# EEC_Capstone-Bottom_Board.net
KiCad netlist of a schematic drawn in EasyEDA
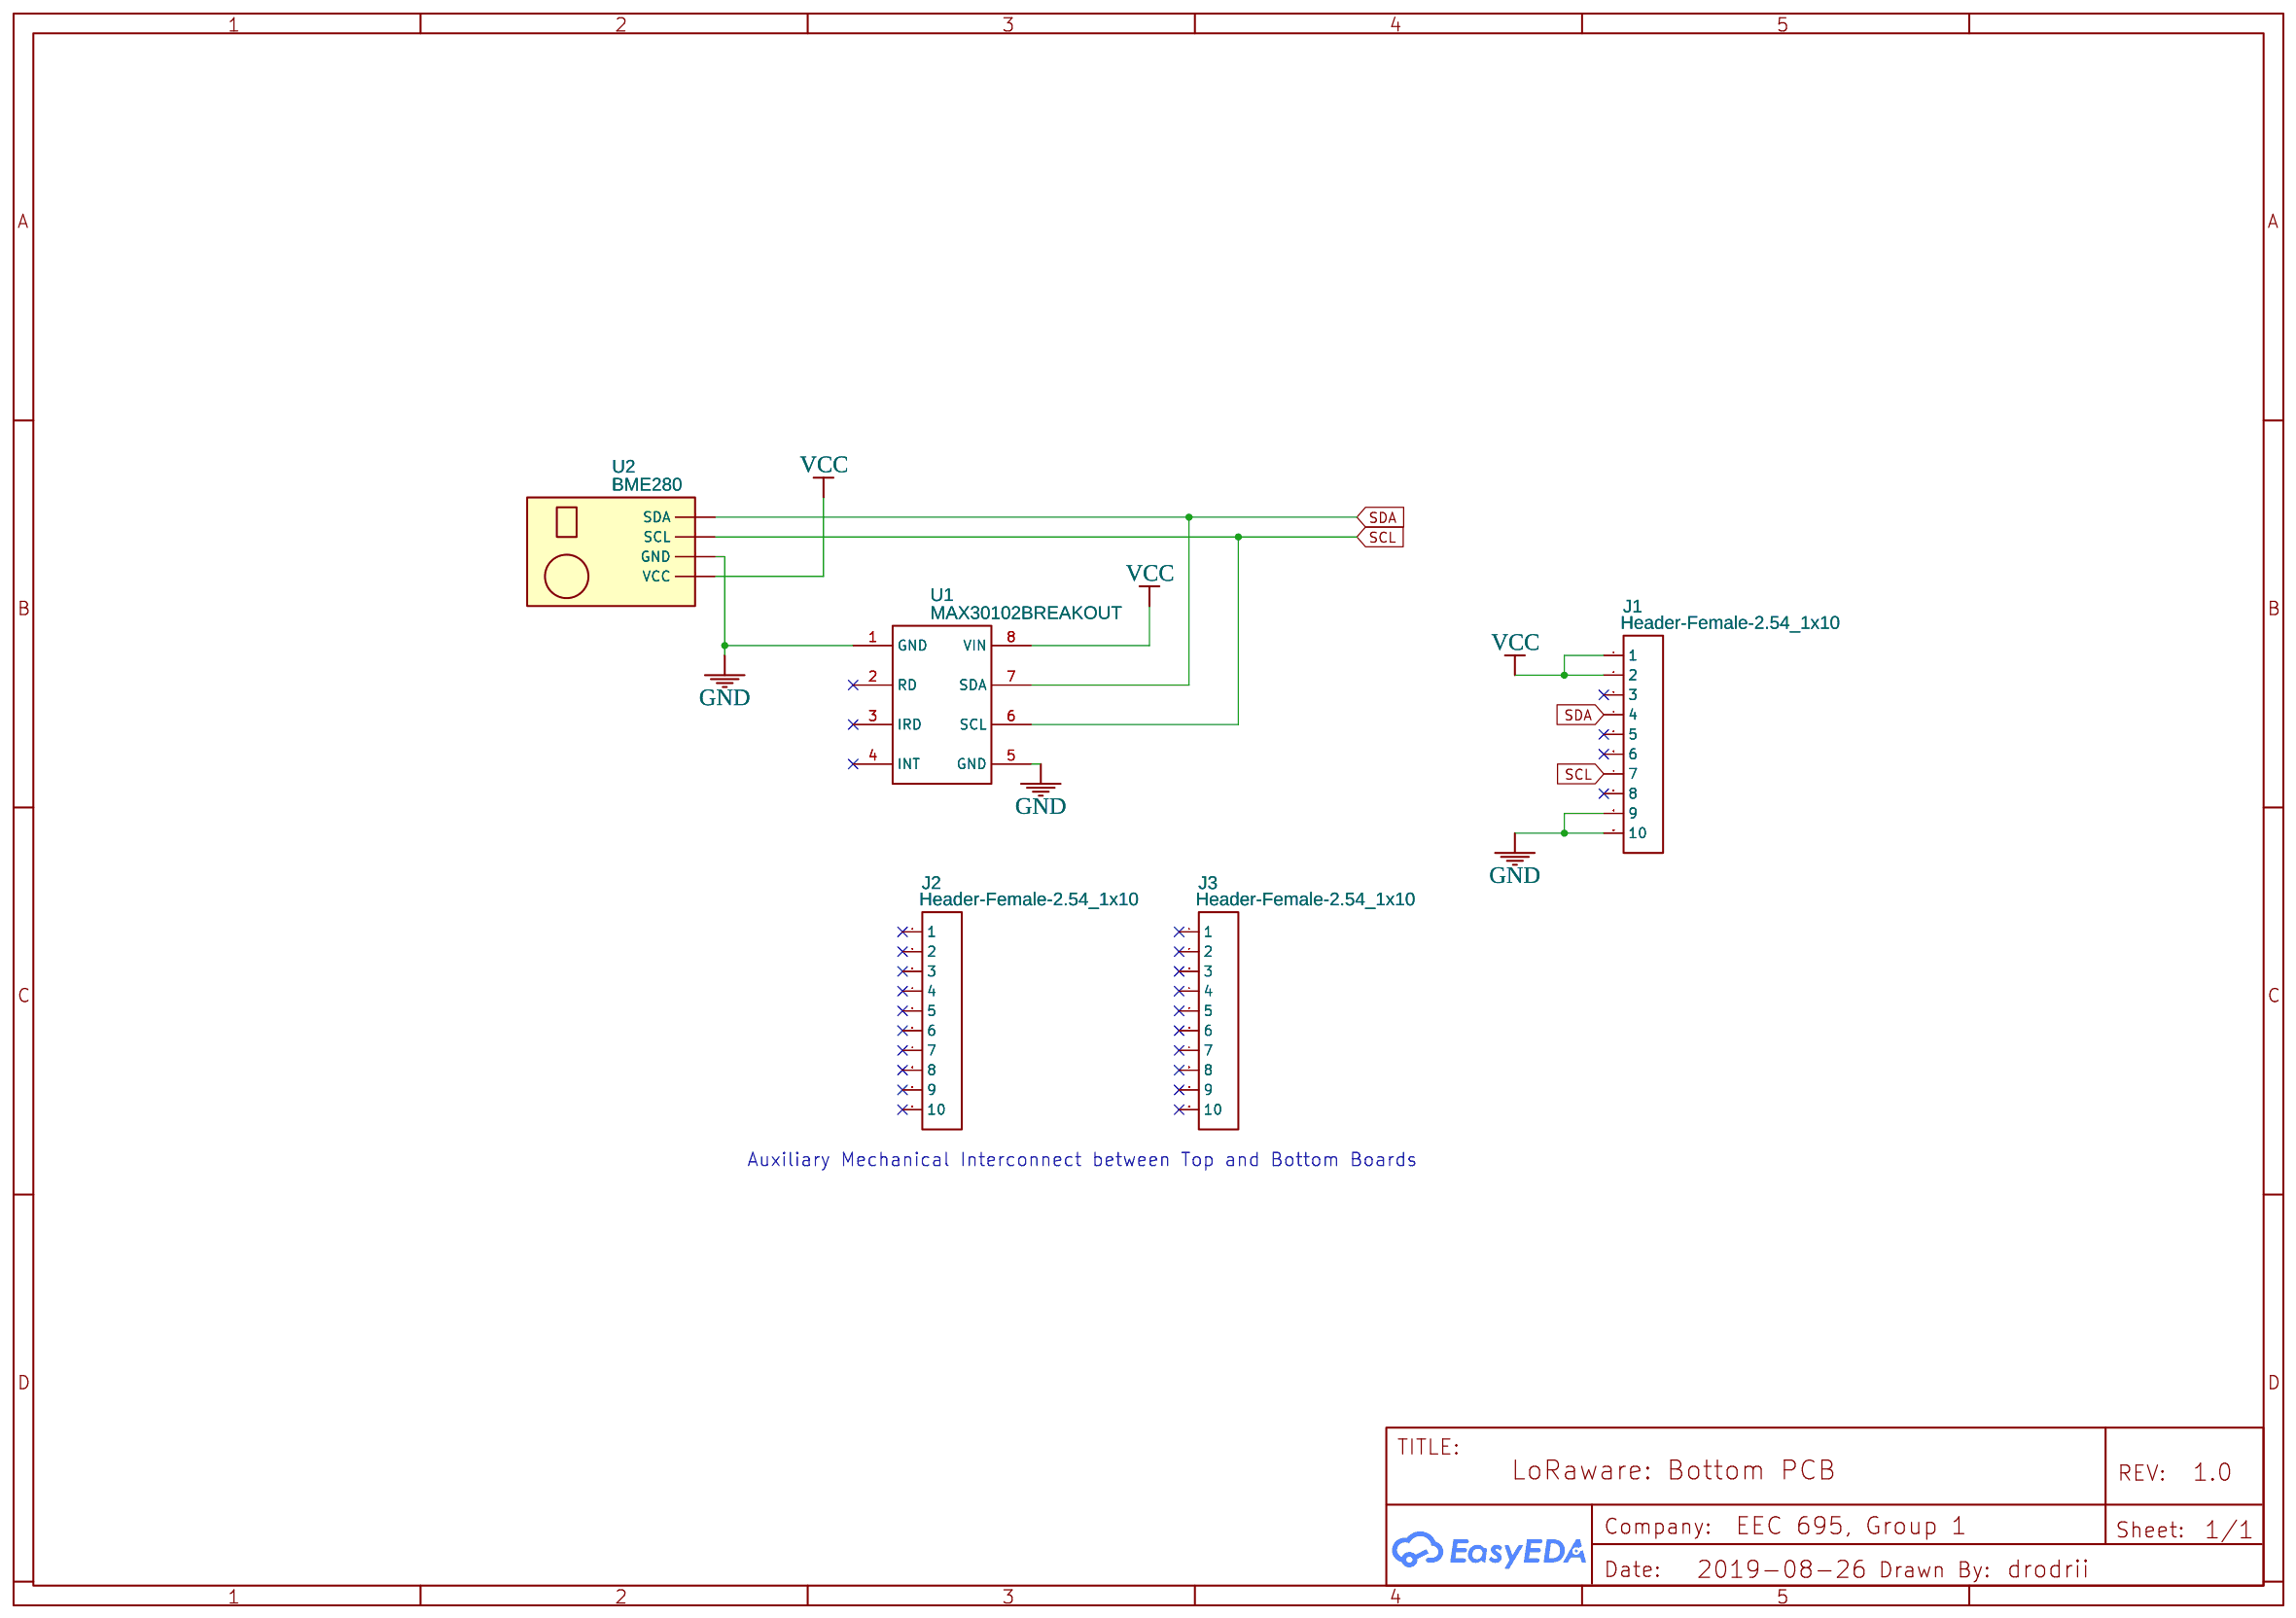
[diagram p0: schematic sheet]

(export (version "E")
  (design (tool "Eeschema 10.0.6"))
  (components
    (comp (ref "J1")
      (value "Header-Female-2.54_1x10")
      (fields
        (field (name "BOM_Manufacturer Part") "2.54mm 1*10P Straight Female header Gold-plated")
        (field (name "BOM_Supplier Part") "C35445")
      )
      (libsource (lib "") (part "Unknown_815_375"))
    )
    (comp (ref "J2")
      (value "Header-Female-2.54_1x10")
      (fields
        (field (name "BOM_Manufacturer Part") "2.54mm 1*10P Straight Female header Gold-plated")
        (field (name "BOM_Supplier Part") "C35445")
      )
      (libsource (lib "") (part "Unknown_460_515"))
    )
    (comp (ref "J3")
      (value "Header-Female-2.54_1x10")
      (fields
        (field (name "BOM_Manufacturer Part") "2.54mm 1*10P Straight Female header Gold-plated")
        (field (name "BOM_Supplier Part") "C35445")
      )
      (libsource (lib "") (part "Unknown_600_515"))
    )
    (comp (ref "U1")
      (value "MAX30102BREAKOUT")
      (fields (field (name "BOM_Manufacturer Part") "MAX30102"))
      (libsource (lib "") (part "Unknown_445_310"))
    )
    (comp (ref "U2") (value "BME280") (libsource (lib "") (part "Unknown_345_275")))
  )
  (nets
    (net (code "1") (name "GND") (class "Default")
      (node (ref "J1") (pin "10") (pinfunction "10_10") (pintype "input"))
      (node (ref "J1") (pin "9") (pinfunction "9_9") (pintype "input"))
      (node (ref "U1") (pin "1") (pinfunction "GND_1") (pintype "unspecified"))
      (node (ref "U1") (pin "5") (pinfunction "GND_5") (pintype "unspecified"))
      (node (ref "U2") (pin "2") (pinfunction "GND_2") (pintype "input"))
    )
    (net (code "2") (name "SCL") (class "Default")
      (node (ref "J1") (pin "7") (pinfunction "7_7") (pintype "input"))
      (node (ref "U1") (pin "6") (pinfunction "SCL_6") (pintype "unspecified"))
      (node (ref "U2") (pin "3") (pinfunction "SCL_3") (pintype "input"))
    )
    (net (code "3") (name "SDA") (class "Default")
      (node (ref "J1") (pin "4") (pinfunction "4_4") (pintype "input"))
      (node (ref "U1") (pin "7") (pinfunction "SDA_7") (pintype "unspecified"))
      (node (ref "U2") (pin "4") (pinfunction "SDA_4") (pintype "input"))
    )
    (net (code "4") (name "VCC") (class "Default")
      (node (ref "J1") (pin "1") (pinfunction "1_1") (pintype "input"))
      (node (ref "J1") (pin "2") (pinfunction "2_2") (pintype "input"))
      (node (ref "U1") (pin "8") (pinfunction "VIN_8") (pintype "unspecified"))
      (node (ref "U2") (pin "1") (pinfunction "VCC_1") (pintype "input"))
    )
    (net (code "5") (name "unconnected-(J1-Pad3)") (class "Default")
      (node (ref "J1") (pin "3") (pinfunction "3_3") (pintype "input+no_connect"))
    )
    (net (code "6") (name "unconnected-(J1-Pad5)") (class "Default")
      (node (ref "J1") (pin "5") (pinfunction "5_5") (pintype "input+no_connect"))
    )
    (net (code "7") (name "unconnected-(J1-Pad6)") (class "Default")
      (node (ref "J1") (pin "6") (pinfunction "6_6") (pintype "input+no_connect"))
    )
    (net (code "8") (name "unconnected-(J1-Pad8)") (class "Default")
      (node (ref "J1") (pin "8") (pinfunction "8_8") (pintype "input+no_connect"))
    )
    (net (code "9") (name "unconnected-(J2-Pad1)") (class "Default")
      (node (ref "J2") (pin "1") (pinfunction "1_1") (pintype "input+no_connect"))
    )
    (net (code "10") (name "unconnected-(J2-Pad2)") (class "Default")
      (node (ref "J2") (pin "2") (pinfunction "2_2") (pintype "input+no_connect"))
    )
    (net (code "11") (name "unconnected-(J2-Pad3)") (class "Default")
      (node (ref "J2") (pin "3") (pinfunction "3_3") (pintype "input+no_connect"))
    )
    (net (code "12") (name "unconnected-(J2-Pad4)") (class "Default")
      (node (ref "J2") (pin "4") (pinfunction "4_4") (pintype "input+no_connect"))
    )
    (net (code "13") (name "unconnected-(J2-Pad5)") (class "Default")
      (node (ref "J2") (pin "5") (pinfunction "5_5") (pintype "input+no_connect"))
    )
    (net (code "14") (name "unconnected-(J2-Pad6)") (class "Default")
      (node (ref "J2") (pin "6") (pinfunction "6_6") (pintype "input+no_connect"))
    )
    (net (code "15") (name "unconnected-(J2-Pad7)") (class "Default")
      (node (ref "J2") (pin "7") (pinfunction "7_7") (pintype "input+no_connect"))
    )
    (net (code "16") (name "unconnected-(J2-Pad8)") (class "Default")
      (node (ref "J2") (pin "8") (pinfunction "8_8") (pintype "input+no_connect"))
    )
    (net (code "17") (name "unconnected-(J2-Pad9)") (class "Default")
      (node (ref "J2") (pin "9") (pinfunction "9_9") (pintype "input+no_connect"))
    )
    (net (code "18") (name "unconnected-(J2-Pad10)") (class "Default")
      (node (ref "J2") (pin "10") (pinfunction "10_10") (pintype "input+no_connect"))
    )
    (net (code "19") (name "unconnected-(J3-Pad1)") (class "Default")
      (node (ref "J3") (pin "1") (pinfunction "1_1") (pintype "input+no_connect"))
    )
    (net (code "20") (name "unconnected-(J3-Pad2)") (class "Default")
      (node (ref "J3") (pin "2") (pinfunction "2_2") (pintype "input+no_connect"))
    )
    (net (code "21") (name "unconnected-(J3-Pad3)") (class "Default")
      (node (ref "J3") (pin "3") (pinfunction "3_3") (pintype "input+no_connect"))
    )
    (net (code "22") (name "unconnected-(J3-Pad4)") (class "Default")
      (node (ref "J3") (pin "4") (pinfunction "4_4") (pintype "input+no_connect"))
    )
    (net (code "23") (name "unconnected-(J3-Pad5)") (class "Default")
      (node (ref "J3") (pin "5") (pinfunction "5_5") (pintype "input+no_connect"))
    )
    (net (code "24") (name "unconnected-(J3-Pad6)") (class "Default")
      (node (ref "J3") (pin "6") (pinfunction "6_6") (pintype "input+no_connect"))
    )
    (net (code "25") (name "unconnected-(J3-Pad7)") (class "Default")
      (node (ref "J3") (pin "7") (pinfunction "7_7") (pintype "input+no_connect"))
    )
    (net (code "26") (name "unconnected-(J3-Pad8)") (class "Default")
      (node (ref "J3") (pin "8") (pinfunction "8_8") (pintype "input+no_connect"))
    )
    (net (code "27") (name "unconnected-(J3-Pad9)") (class "Default")
      (node (ref "J3") (pin "9") (pinfunction "9_9") (pintype "input+no_connect"))
    )
    (net (code "28") (name "unconnected-(J3-Pad10)") (class "Default")
      (node (ref "J3") (pin "10") (pinfunction "10_10") (pintype "input+no_connect"))
    )
    (net (code "29") (name "unconnected-(U1-INT-Pad4)") (class "Default")
      (node (ref "U1") (pin "4") (pinfunction "INT_4") (pintype "unspecified+no_connect"))
    )
    (net (code "30") (name "unconnected-(U1-IRD-Pad3)") (class "Default")
      (node (ref "U1") (pin "3") (pinfunction "IRD_3") (pintype "unspecified+no_connect"))
    )
    (net (code "31") (name "unconnected-(U1-RD-Pad2)") (class "Default")
      (node (ref "U1") (pin "2") (pinfunction "RD_2") (pintype "unspecified+no_connect"))
    )
  )
)
